# 11_-_Power_Input_and_Output_regulator.net
KiCad netlist of a schematic drawn in Altium Designer
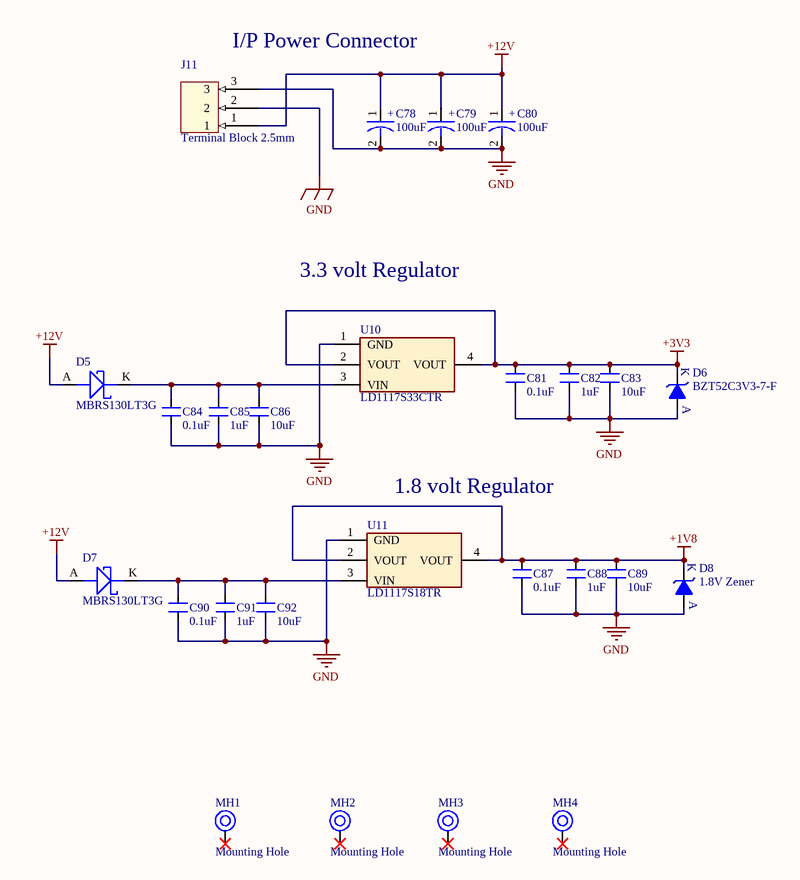
[diagram p0: [11]- Power Input and Output regulator.SchDoc]

(export (version "E")
  (design (tool "Eeschema 10.0.6"))
  (components
    (comp (ref "C78")
      (value "100uF")
      (footprint "ACAP_P305_D393_H393_RAD")
      (description "100µF 50V Aluminum Polymer Capacitor Radial, Can - SMD 28mOhm 4000 Hrs @ 125°C")
      (fields
        (field (name "MANUFACTURER") "Nichicon")
        (field (name "MANUFACTURER PART NUMBER") "GYA1H101MCQ1GS")
      )
      (libsource (lib "ESTEEMPCBLIB") (part "CAP-P_100uF-50V-20%-RAD"))
    )
    (comp (ref "C79")
      (value "100uF")
      (footprint "ACAP_P305_D393_H393_RAD")
      (description "100µF 50V Aluminum Polymer Capacitor Radial, Can - SMD 28mOhm 4000 Hrs @ 125°C")
      (fields
        (field (name "MANUFACTURER") "Nichicon")
        (field (name "MANUFACTURER PART NUMBER") "GYA1H101MCQ1GS")
      )
      (libsource (lib "ESTEEMPCBLIB") (part "CAP-P_100uF-50V-20%-RAD"))
    )
    (comp (ref "C80")
      (value "100uF")
      (footprint "ACAP_P305_D393_H393_RAD")
      (description "100µF 50V Aluminum Polymer Capacitor Radial, Can - SMD 28mOhm 4000 Hrs @ 125°C")
      (fields
        (field (name "MANUFACTURER") "Nichicon")
        (field (name "MANUFACTURER PART NUMBER") "GYA1H101MCQ1GS")
      )
      (libsource (lib "ESTEEMPCBLIB") (part "CAP-P_100uF-50V-20%-RAD"))
    )
    (comp (ref "C81")
      (value "0.1uF")
      (footprint "CAP_0805")
      (description "0.1µF ±10% 50V Ceramic Capacitor X7R 0805 (2012 Metric)")
      (fields
        (field (name "MANUFACTURER") "Samsung")
        (field (name "MANUFACTURER PART NUMBER") "CL21B104KBCNNNC")
      )
      (libsource (lib "ESTEEMPCBLIB") (part "CAP_0.1uF-50V-10%-0805"))
    )
    (comp (ref "C82")
      (value "1uF")
      (footprint "CAP_0805")
      (description "1µF ±5% 50V Ceramic Capacitor X7R 0805 (2012 Metric)")
      (fields
        (field (name "MANUFACTURER") "Samsung")
        (field (name "MANUFACTURER PART NUMBER") "CC0805JKX7R9BB105")
      )
      (libsource (lib "ESTEEMPCBLIB") (part "CAP_1uF-50V-5%-0805"))
    )
    (comp (ref "C83")
      (value "10uF")
      (footprint "CAP_1206")
      (description "10µF ±10% 50V Ceramic Capacitor X7R 1206 (3216 Metric)")
      (fields
        (field (name "MANUFACTURER") "KEMET")
        (field (name "MANUFACTURER PART NUMBER") "CL31B106KBHNNNE")
      )
      (libsource (lib "ESTEEMPCBLIB") (part "CAP_10uF-50V-10%-1206"))
    )
    (comp (ref "C84")
      (value "0.1uF")
      (footprint "CAP_0805")
      (description "0.1µF ±10% 50V Ceramic Capacitor X7R 0805 (2012 Metric)")
      (fields
        (field (name "MANUFACTURER") "Samsung")
        (field (name "MANUFACTURER PART NUMBER") "CL21B104KBCNNNC")
      )
      (libsource (lib "ESTEEMPCBLIB") (part "CAP_0.1uF-50V-10%-0805"))
    )
    (comp (ref "C85")
      (value "1uF")
      (footprint "CAP_0805")
      (description "1µF ±5% 50V Ceramic Capacitor X7R 0805 (2012 Metric)")
      (fields
        (field (name "MANUFACTURER") "Samsung")
        (field (name "MANUFACTURER PART NUMBER") "CC0805JKX7R9BB105")
      )
      (libsource (lib "ESTEEMPCBLIB") (part "CAP_1uF-50V-5%-0805"))
    )
    (comp (ref "C86")
      (value "10uF")
      (footprint "CAP_1206")
      (description "10µF ±10% 50V Ceramic Capacitor X7R 1206 (3216 Metric)")
      (fields
        (field (name "MANUFACTURER") "KEMET")
        (field (name "MANUFACTURER PART NUMBER") "CL31B106KBHNNNE")
      )
      (libsource (lib "ESTEEMPCBLIB") (part "CAP_10uF-50V-10%-1206"))
    )
    (comp (ref "C87")
      (value "0.1uF")
      (footprint "CAP_0805")
      (description "0.1µF ±10% 50V Ceramic Capacitor X7R 0805 (2012 Metric)")
      (fields
        (field (name "MANUFACTURER") "Samsung")
        (field (name "MANUFACTURER PART NUMBER") "CL21B104KBCNNNC")
      )
      (libsource (lib "ESTEEMPCBLIB") (part "CAP_0.1uF-50V-10%-0805"))
    )
    (comp (ref "C88")
      (value "1uF")
      (footprint "CAP_0805")
      (description "1µF ±5% 50V Ceramic Capacitor X7R 0805 (2012 Metric)")
      (fields
        (field (name "MANUFACTURER") "Samsung")
        (field (name "MANUFACTURER PART NUMBER") "CC0805JKX7R9BB105")
      )
      (libsource (lib "ESTEEMPCBLIB") (part "CAP_1uF-50V-5%-0805"))
    )
    (comp (ref "C89")
      (value "10uF")
      (footprint "CAP_1206")
      (description "10µF ±10% 50V Ceramic Capacitor X7R 1206 (3216 Metric)")
      (fields
        (field (name "MANUFACTURER") "KEMET")
        (field (name "MANUFACTURER PART NUMBER") "CL31B106KBHNNNE")
      )
      (libsource (lib "ESTEEMPCBLIB") (part "CAP_10uF-50V-10%-1206"))
    )
    (comp (ref "C90")
      (value "0.1uF")
      (footprint "CAP_0805")
      (description "0.1µF ±10% 50V Ceramic Capacitor X7R 0805 (2012 Metric)")
      (fields
        (field (name "MANUFACTURER") "Samsung")
        (field (name "MANUFACTURER PART NUMBER") "CL21B104KBCNNNC")
      )
      (libsource (lib "ESTEEMPCBLIB") (part "CAP_0.1uF-50V-10%-0805"))
    )
    (comp (ref "C91")
      (value "1uF")
      (footprint "CAP_0805")
      (description "1µF ±5% 50V Ceramic Capacitor X7R 0805 (2012 Metric)")
      (fields
        (field (name "MANUFACTURER") "Samsung")
        (field (name "MANUFACTURER PART NUMBER") "CC0805JKX7R9BB105")
      )
      (libsource (lib "ESTEEMPCBLIB") (part "CAP_1uF-50V-5%-0805"))
    )
    (comp (ref "C92")
      (value "10uF")
      (footprint "CAP_1206")
      (description "10µF ±10% 50V Ceramic Capacitor X7R 1206 (3216 Metric)")
      (fields
        (field (name "MANUFACTURER") "KEMET")
        (field (name "MANUFACTURER PART NUMBER") "CL31B106KBHNNNE")
      )
      (libsource (lib "ESTEEMPCBLIB") (part "CAP_10uF-50V-10%-1206"))
    )
    (comp (ref "D5")
      (value "MBRS130LT3G")
      (footprint "DIO_SMB_DO-214AA")
      (description "Diode Schottky 30V 2A Surface Mount SMB")
      (fields (field (name "MANUFACTURER") "ON Semiconductor"))
      (libsource (lib "ESTEEMPCBLIB") (part "DIO-S_445mV-30V-2A-SMB"))
    )
    (comp (ref "D6")
      (value "BZT52C3V3-7-F")
      (footprint "DIO_SOD-123")
      (description "Zener Diode 3.3V 500mW ±6% Surface Mount SOD-123")
      (fields (field (name "MANUFACTURER") "Diodes Incorporated"))
      (libsource (lib "ESTEEMPCBLIB") (part "DIO-Z_3.3V-500mW-SOD123"))
    )
    (comp (ref "D7")
      (value "MBRS130LT3G")
      (footprint "DIO_SMB_DO-214AA")
      (description "Diode Schottky 30V 2A Surface Mount SMB")
      (fields (field (name "MANUFACTURER") "ON Semiconductor"))
      (libsource (lib "ESTEEMPCBLIB") (part "DIO-S_445mV-30V-2A-SMB"))
    )
    (comp (ref "D8")
      (value "1.8V Zener")
      (footprint "DIO_DO-213AB_SMD")
      (description "Zener Diode 1.8V 500mW ±5% Surface Mount DO-213AA")
      (libsource (lib "ESTEEMPCBLIB") (part "DIO-Z_1.8V-500mW-DO213AA"))
    )
    (comp (ref "J11")
      (value "Terminal Block 2.5mm")
      (footprint "CON3_100_TB_TH_ST")
      (description "3 Pins, 1 Row 2.54mm Pitch, straight Connector, male")
      (fields
        (field (name "MANUFACTURER PART NUMBER") "1725669")
        (field (name "MANUFACTURER") "Phoenix Contact")
      )
      (libsource (lib "ESTEEMPCBLIB") (part "CON-TB_3X1-100-ST-TH"))
    )
    (comp (ref "MH1")
      (value "Mounting Hole")
      (footprint "MOUNTING")
      (fields (field (name "MANUFACTURER PART NUMBER") "NA"))
      (libsource (lib "ESTEEMPCBLIB") (part "MH_3.5H_6D"))
    )
    (comp (ref "MH2")
      (value "Mounting Hole")
      (footprint "MOUNTING")
      (fields (field (name "MANUFACTURER PART NUMBER") "NA"))
      (libsource (lib "ESTEEMPCBLIB") (part "MH_3.5H_6D"))
    )
    (comp (ref "MH3")
      (value "Mounting Hole")
      (footprint "MOUNTING")
      (fields (field (name "MANUFACTURER PART NUMBER") "NA"))
      (libsource (lib "ESTEEMPCBLIB") (part "MH_3.5H_6D"))
    )
    (comp (ref "MH4")
      (value "Mounting Hole")
      (footprint "MOUNTING")
      (fields (field (name "MANUFACTURER PART NUMBER") "NA"))
      (libsource (lib "ESTEEMPCBLIB") (part "MH_3.5H_6D"))
    )
    (comp (ref "U10")
      (value "LD1117S33CTR")
      (footprint "SOT223_3")
      (description "Linear Voltage Regulator IC 1 Output 800mA SOT-223")
      (fields (field (name "MANUFACTURER") "STMicroelectronics"))
      (libsource (lib "ESTEEMPCBLIB") (part "REG_15V-3.3V-0.9A-12W-SOT223"))
    )
    (comp (ref "U11")
      (value "LD1117S18TR")
      (footprint "SOT223_3")
      (description "LDO Voltage Regulators 1.8V 0.8A Positive")
      (fields (field (name "MANUFACTURER") "STMicroelectronics"))
      (libsource (lib "ESTEEMPCBLIB") (part "REG_15V-1.8V-0.8A-1.4W-SOT223"))
    )
  )
  (nets
    (net (code "1") (name "+1V8") (class "Default")
      (node (ref "C87") (pin "1") (pinfunction "1_1") (pintype "passive"))
      (node (ref "C88") (pin "2") (pinfunction "2_2") (pintype "passive"))
      (node (ref "C89") (pin "2") (pinfunction "2_2") (pintype "passive"))
      (node (ref "D8") (pin "K") (pinfunction "K_K") (pintype "passive"))
      (node (ref "U11") (pin "2") (pinfunction "VOUT_2") (pintype "passive"))
      (node (ref "U11") (pin "4") (pinfunction "VOUT_4") (pintype "passive"))
    )
    (net (code "2") (name "+3V3") (class "Default")
      (node (ref "C81") (pin "1") (pinfunction "1_1") (pintype "passive"))
      (node (ref "C82") (pin "2") (pinfunction "2_2") (pintype "passive"))
      (node (ref "C83") (pin "2") (pinfunction "2_2") (pintype "passive"))
      (node (ref "D6") (pin "K") (pinfunction "K_K") (pintype "passive"))
      (node (ref "U10") (pin "2") (pinfunction "VOUT_2") (pintype "passive"))
      (node (ref "U10") (pin "4") (pinfunction "VOUT_4") (pintype "passive"))
    )
    (net (code "3") (name "+12V") (class "Default")
      (node (ref "C78") (pin "1") (pinfunction "1_1") (pintype "passive"))
      (node (ref "C79") (pin "1") (pinfunction "1_1") (pintype "passive"))
      (node (ref "C80") (pin "1") (pinfunction "1_1") (pintype "passive"))
      (node (ref "D5") (pin "A") (pinfunction "A_A") (pintype "passive"))
      (node (ref "D7") (pin "A") (pinfunction "A_A") (pintype "passive"))
      (node (ref "J11") (pin "1") (pinfunction "1_1") (pintype "input"))
    )
    (net (code "4") (name "GND") (class "Default")
      (node (ref "C78") (pin "2") (pinfunction "2_2") (pintype "passive"))
      (node (ref "C79") (pin "2") (pinfunction "2_2") (pintype "passive"))
      (node (ref "C80") (pin "2") (pinfunction "2_2") (pintype "passive"))
      (node (ref "C81") (pin "2") (pinfunction "2_2") (pintype "passive"))
      (node (ref "C82") (pin "1") (pinfunction "1_1") (pintype "passive"))
      (node (ref "C83") (pin "1") (pinfunction "1_1") (pintype "passive"))
      (node (ref "C84") (pin "2") (pinfunction "2_2") (pintype "passive"))
      (node (ref "C85") (pin "1") (pinfunction "1_1") (pintype "passive"))
      (node (ref "C86") (pin "1") (pinfunction "1_1") (pintype "passive"))
      (node (ref "C87") (pin "2") (pinfunction "2_2") (pintype "passive"))
      (node (ref "C88") (pin "1") (pinfunction "1_1") (pintype "passive"))
      (node (ref "C89") (pin "1") (pinfunction "1_1") (pintype "passive"))
      (node (ref "C90") (pin "2") (pinfunction "2_2") (pintype "passive"))
      (node (ref "C91") (pin "1") (pinfunction "1_1") (pintype "passive"))
      (node (ref "C92") (pin "1") (pinfunction "1_1") (pintype "passive"))
      (node (ref "D6") (pin "A") (pinfunction "A_A") (pintype "passive"))
      (node (ref "D8") (pin "A") (pinfunction "A_A") (pintype "passive"))
      (node (ref "J11") (pin "2") (pinfunction "2_2") (pintype "input"))
      (node (ref "J11") (pin "3") (pinfunction "3_3") (pintype "input"))
      (node (ref "U10") (pin "1") (pinfunction "GND_1") (pintype "passive"))
      (node (ref "U11") (pin "1") (pinfunction "GND_1") (pintype "passive"))
    )
    (net (code "5") (name "Net-(U10-VIN)") (class "Default")
      (node (ref "C84") (pin "1") (pinfunction "1_1") (pintype "passive"))
      (node (ref "C85") (pin "2") (pinfunction "2_2") (pintype "passive"))
      (node (ref "C86") (pin "2") (pinfunction "2_2") (pintype "passive"))
      (node (ref "D5") (pin "K") (pinfunction "K_K") (pintype "passive"))
      (node (ref "U10") (pin "3") (pinfunction "VIN_3") (pintype "passive"))
    )
    (net (code "6") (name "Net-(U11-VIN)") (class "Default")
      (node (ref "C90") (pin "1") (pinfunction "1_1") (pintype "passive"))
      (node (ref "C91") (pin "2") (pinfunction "2_2") (pintype "passive"))
      (node (ref "C92") (pin "2") (pinfunction "2_2") (pintype "passive"))
      (node (ref "D7") (pin "K") (pinfunction "K_K") (pintype "passive"))
      (node (ref "U11") (pin "3") (pinfunction "VIN_3") (pintype "passive"))
    )
    (net (code "7") (name "unconnected-(MH1-Pad1)") (class "Default")
      (node (ref "MH1") (pin "1") (pinfunction "1_1") (pintype "passive+no_connect"))
    )
    (net (code "8") (name "unconnected-(MH2-Pad1)") (class "Default")
      (node (ref "MH2") (pin "1") (pinfunction "1_1") (pintype "passive+no_connect"))
    )
    (net (code "9") (name "unconnected-(MH3-Pad1)") (class "Default")
      (node (ref "MH3") (pin "1") (pinfunction "1_1") (pintype "passive+no_connect"))
    )
    (net (code "10") (name "unconnected-(MH4-Pad1)") (class "Default")
      (node (ref "MH4") (pin "1") (pinfunction "1_1") (pintype "passive+no_connect"))
    )
  )
)
